# SCH_DTACK_Card_16_DIP_2023-08-05_Altium.net
KiCad netlist of a schematic drawn in Altium Designer
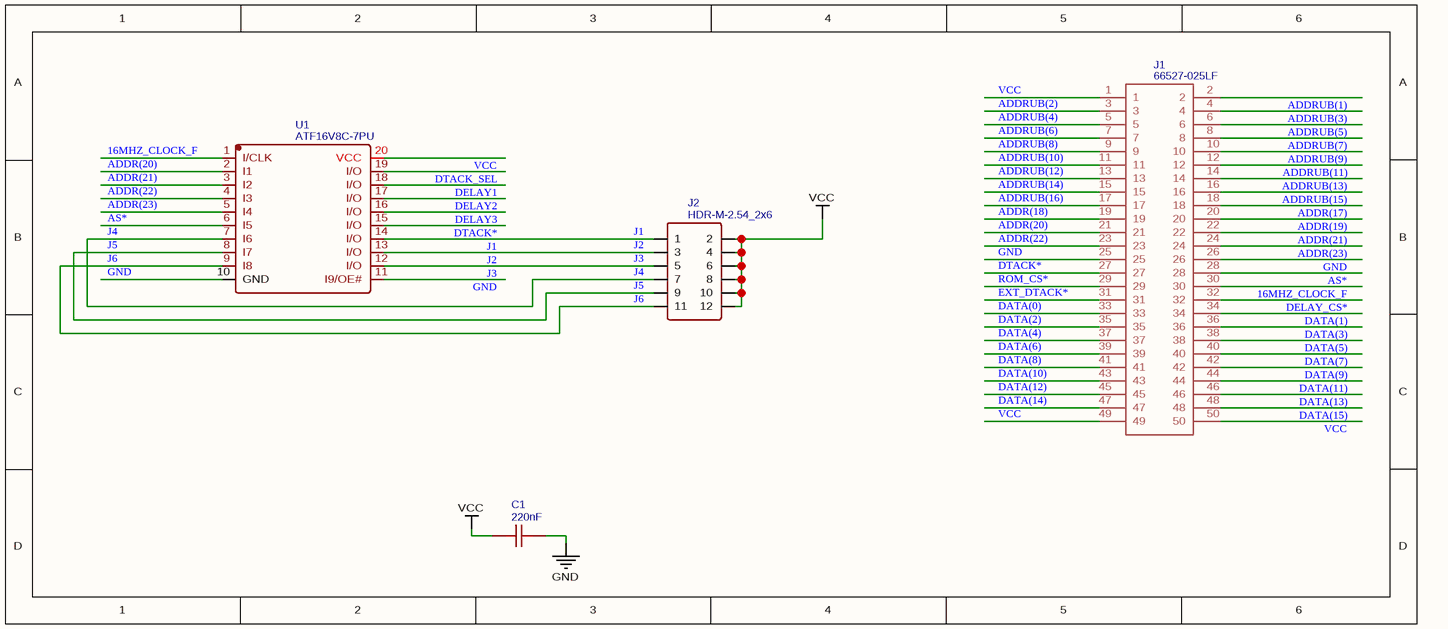
[diagram p0: SCH_DTACK Card 16 DIP_2023-08-05_Altium.schdoc]

(export (version "E")
  (design (tool "Eeschema 10.0.6"))
  (components
    (comp (ref "C1")
      (value "220nF")
      (fields (field (name "MANUFACTURER") "TDK") (field (name "CONTRIBUTOR") "LCSC"))
      (libsource (lib "altium-import") (part "root_0_220nF_"))
    )
    (comp (ref "J1")
      (value "66527-025LF")
      (fields (field (name "CONTRIBUTOR") "rezafouladian"))
      (libsource (lib "altium-import") (part "root_0_66527-025LF_"))
    )
    (comp (ref "J2")
      (value "HDR-M-2.54_2x6")
      (fields (field (name "CONTRIBUTOR") "LCEDA_Lib"))
      (libsource (lib "altium-import") (part "root_0_HDR-M-2.54_2x6_"))
    )
    (comp (ref "U1")
      (value "ATF16V8C-7PU")
      (fields (field (name "MANUFACTURER") "MICROCHIP(美国微芯)") (field (name "CONTRIBUTOR") "LCSC"))
      (libsource (lib "altium-import") (part "root_0_ATF16V8C-7PU_"))
    )
  )
  (nets
    (net (code "1") (name "/16MHZ_CLOCK_F") (class "Default")
      (node (ref "J1") (pin "30") (pinfunction "30_30") (pintype "passive"))
      (node (ref "U1") (pin "1") (pinfunction "I/CLK_1") (pintype "passive"))
    )
    (net (code "2") (name "/ADDR(17)") (class "Default")
      (node (ref "J1") (pin "18") (pinfunction "18_18") (pintype "passive"))
    )
    (net (code "3") (name "/ADDR(18)") (class "Default")
      (node (ref "J1") (pin "19") (pinfunction "19_19") (pintype "passive"))
    )
    (net (code "4") (name "/ADDR(19)") (class "Default")
      (node (ref "J1") (pin "20") (pinfunction "20_20") (pintype "passive"))
    )
    (net (code "5") (name "/ADDR(20)") (class "Default")
      (node (ref "J1") (pin "21") (pinfunction "21_21") (pintype "passive"))
      (node (ref "U1") (pin "2") (pinfunction "I1_2") (pintype "passive"))
    )
    (net (code "6") (name "/ADDR(21)") (class "Default")
      (node (ref "J1") (pin "22") (pinfunction "22_22") (pintype "passive"))
      (node (ref "U1") (pin "3") (pinfunction "I2_3") (pintype "passive"))
    )
    (net (code "7") (name "/ADDR(22)") (class "Default")
      (node (ref "J1") (pin "23") (pinfunction "23_23") (pintype "passive"))
      (node (ref "U1") (pin "4") (pinfunction "I3_4") (pintype "passive"))
    )
    (net (code "8") (name "/ADDR(23)") (class "Default")
      (node (ref "J1") (pin "24") (pinfunction "24_24") (pintype "passive"))
      (node (ref "U1") (pin "5") (pinfunction "I4_5") (pintype "passive"))
    )
    (net (code "9") (name "/ADDRUB(1)") (class "Default")
      (node (ref "J1") (pin "2") (pinfunction "2_2") (pintype "passive"))
    )
    (net (code "10") (name "/ADDRUB(2)") (class "Default")
      (node (ref "J1") (pin "3") (pinfunction "3_3") (pintype "passive"))
    )
    (net (code "11") (name "/ADDRUB(3)") (class "Default")
      (node (ref "J1") (pin "4") (pinfunction "4_4") (pintype "passive"))
    )
    (net (code "12") (name "/ADDRUB(4)") (class "Default")
      (node (ref "J1") (pin "5") (pinfunction "5_5") (pintype "passive"))
    )
    (net (code "13") (name "/ADDRUB(5)") (class "Default")
      (node (ref "J1") (pin "6") (pinfunction "6_6") (pintype "passive"))
    )
    (net (code "14") (name "/ADDRUB(6)") (class "Default")
      (node (ref "J1") (pin "7") (pinfunction "7_7") (pintype "passive"))
    )
    (net (code "15") (name "/ADDRUB(7)") (class "Default")
      (node (ref "J1") (pin "8") (pinfunction "8_8") (pintype "passive"))
    )
    (net (code "16") (name "/ADDRUB(8)") (class "Default")
      (node (ref "J1") (pin "9") (pinfunction "9_9") (pintype "passive"))
    )
    (net (code "17") (name "/ADDRUB(9)") (class "Default")
      (node (ref "J1") (pin "10") (pinfunction "10_10") (pintype "passive"))
    )
    (net (code "18") (name "/ADDRUB(10)") (class "Default")
      (node (ref "J1") (pin "11") (pinfunction "11_11") (pintype "passive"))
    )
    (net (code "19") (name "/ADDRUB(11)") (class "Default")
      (node (ref "J1") (pin "12") (pinfunction "12_12") (pintype "passive"))
    )
    (net (code "20") (name "/ADDRUB(12)") (class "Default")
      (node (ref "J1") (pin "13") (pinfunction "13_13") (pintype "passive"))
    )
    (net (code "21") (name "/ADDRUB(13)") (class "Default")
      (node (ref "J1") (pin "14") (pinfunction "14_14") (pintype "passive"))
    )
    (net (code "22") (name "/ADDRUB(14)") (class "Default")
      (node (ref "J1") (pin "15") (pinfunction "15_15") (pintype "passive"))
    )
    (net (code "23") (name "/ADDRUB(15)") (class "Default")
      (node (ref "J1") (pin "16") (pinfunction "16_16") (pintype "passive"))
    )
    (net (code "24") (name "/ADDRUB(16)") (class "Default")
      (node (ref "J1") (pin "17") (pinfunction "17_17") (pintype "passive"))
    )
    (net (code "25") (name "/AS*") (class "Default")
      (node (ref "J1") (pin "28") (pinfunction "28_28") (pintype "passive"))
      (node (ref "U1") (pin "6") (pinfunction "I5_6") (pintype "passive"))
    )
    (net (code "26") (name "/DATA(0)") (class "Default")
      (node (ref "J1") (pin "33") (pinfunction "33_33") (pintype "passive"))
    )
    (net (code "27") (name "/DATA(1)") (class "Default")
      (node (ref "J1") (pin "34") (pinfunction "34_34") (pintype "passive"))
    )
    (net (code "28") (name "/DATA(2)") (class "Default")
      (node (ref "J1") (pin "35") (pinfunction "35_35") (pintype "passive"))
    )
    (net (code "29") (name "/DATA(3)") (class "Default")
      (node (ref "J1") (pin "36") (pinfunction "36_36") (pintype "passive"))
    )
    (net (code "30") (name "/DATA(4)") (class "Default")
      (node (ref "J1") (pin "37") (pinfunction "37_37") (pintype "passive"))
    )
    (net (code "31") (name "/DATA(5)") (class "Default")
      (node (ref "J1") (pin "38") (pinfunction "38_38") (pintype "passive"))
    )
    (net (code "32") (name "/DATA(6)") (class "Default")
      (node (ref "J1") (pin "39") (pinfunction "39_39") (pintype "passive"))
    )
    (net (code "33") (name "/DATA(7)") (class "Default")
      (node (ref "J1") (pin "40") (pinfunction "40_40") (pintype "passive"))
    )
    (net (code "34") (name "/DATA(8)") (class "Default")
      (node (ref "J1") (pin "41") (pinfunction "41_41") (pintype "passive"))
    )
    (net (code "35") (name "/DATA(9)") (class "Default")
      (node (ref "J1") (pin "42") (pinfunction "42_42") (pintype "passive"))
    )
    (net (code "36") (name "/DATA(10)") (class "Default")
      (node (ref "J1") (pin "43") (pinfunction "43_43") (pintype "passive"))
    )
    (net (code "37") (name "/DATA(11)") (class "Default")
      (node (ref "J1") (pin "44") (pinfunction "44_44") (pintype "passive"))
    )
    (net (code "38") (name "/DATA(12)") (class "Default")
      (node (ref "J1") (pin "45") (pinfunction "45_45") (pintype "passive"))
    )
    (net (code "39") (name "/DATA(13)") (class "Default")
      (node (ref "J1") (pin "46") (pinfunction "46_46") (pintype "passive"))
    )
    (net (code "40") (name "/DATA(14)") (class "Default")
      (node (ref "J1") (pin "47") (pinfunction "47_47") (pintype "passive"))
    )
    (net (code "41") (name "/DATA(15)") (class "Default")
      (node (ref "J1") (pin "48") (pinfunction "48_48") (pintype "passive"))
    )
    (net (code "42") (name "/DELAY1") (class "Default")
      (node (ref "U1") (pin "18") (pinfunction "I/O_18") (pintype "passive"))
    )
    (net (code "43") (name "/DELAY2") (class "Default")
      (node (ref "U1") (pin "17") (pinfunction "I/O_17") (pintype "passive"))
    )
    (net (code "44") (name "/DELAY3") (class "Default")
      (node (ref "U1") (pin "16") (pinfunction "I/O_16") (pintype "passive"))
    )
    (net (code "45") (name "/DELAY_CS*") (class "Default")
      (node (ref "J1") (pin "32") (pinfunction "32_32") (pintype "passive"))
    )
    (net (code "46") (name "/DTACK*") (class "Default")
      (node (ref "J1") (pin "27") (pinfunction "27_27") (pintype "passive"))
      (node (ref "U1") (pin "15") (pinfunction "I/O_15") (pintype "passive"))
    )
    (net (code "47") (name "/DTACK_SEL") (class "Default")
      (node (ref "U1") (pin "19") (pinfunction "I/O_19") (pintype "passive"))
    )
    (net (code "48") (name "/EXT_DTACK*") (class "Default")
      (node (ref "J1") (pin "31") (pinfunction "31_31") (pintype "passive"))
    )
    (net (code "49") (name "/J1") (class "Default")
      (node (ref "J2") (pin "1") (pinfunction "1_1") (pintype "passive"))
      (node (ref "U1") (pin "14") (pinfunction "I/O_14") (pintype "passive"))
    )
    (net (code "50") (name "/J2") (class "Default")
      (node (ref "J2") (pin "3") (pinfunction "3_3") (pintype "passive"))
      (node (ref "U1") (pin "13") (pinfunction "I/O_13") (pintype "passive"))
    )
    (net (code "51") (name "/J3") (class "Default")
      (node (ref "J2") (pin "5") (pinfunction "5_5") (pintype "passive"))
      (node (ref "U1") (pin "12") (pinfunction "I/O_12") (pintype "passive"))
    )
    (net (code "52") (name "/J4") (class "Default")
      (node (ref "J2") (pin "7") (pinfunction "7_7") (pintype "passive"))
      (node (ref "U1") (pin "7") (pinfunction "I6_7") (pintype "passive"))
    )
    (net (code "53") (name "/J5") (class "Default")
      (node (ref "J2") (pin "9") (pinfunction "9_9") (pintype "passive"))
      (node (ref "U1") (pin "8") (pinfunction "I7_8") (pintype "passive"))
    )
    (net (code "54") (name "/J6") (class "Default")
      (node (ref "J2") (pin "11") (pinfunction "11_11") (pintype "passive"))
      (node (ref "U1") (pin "9") (pinfunction "I8_9") (pintype "passive"))
    )
    (net (code "55") (name "/ROM_CS*") (class "Default")
      (node (ref "J1") (pin "29") (pinfunction "29_29") (pintype "passive"))
    )
    (net (code "56") (name "GND") (class "Default")
      (node (ref "C1") (pin "2") (pinfunction "2_2") (pintype "passive"))
      (node (ref "J1") (pin "25") (pinfunction "25_25") (pintype "passive"))
      (node (ref "J1") (pin "26") (pinfunction "26_26") (pintype "passive"))
      (node (ref "U1") (pin "10") (pinfunction "GND_10") (pintype "passive"))
      (node (ref "U1") (pin "11") (pinfunction "I9/OE#_11") (pintype "passive"))
    )
    (net (code "57") (name "VCC") (class "Default")
      (node (ref "C1") (pin "1") (pinfunction "1_1") (pintype "passive"))
      (node (ref "J1") (pin "1") (pinfunction "1_1") (pintype "passive"))
      (node (ref "J1") (pin "49") (pinfunction "49_49") (pintype "passive"))
      (node (ref "J1") (pin "50") (pinfunction "50_50") (pintype "passive"))
      (node (ref "J2") (pin "10") (pinfunction "10_10") (pintype "passive"))
      (node (ref "J2") (pin "12") (pinfunction "12_12") (pintype "passive"))
      (node (ref "J2") (pin "2") (pinfunction "2_2") (pintype "passive"))
      (node (ref "J2") (pin "4") (pinfunction "4_4") (pintype "passive"))
      (node (ref "J2") (pin "6") (pinfunction "6_6") (pintype "passive"))
      (node (ref "J2") (pin "8") (pinfunction "8_8") (pintype "passive"))
      (node (ref "U1") (pin "20") (pinfunction "VCC_20") (pintype "passive"))
    )
  )
)
